# Temp_Bank.net
KiCad netlist of a schematic drawn in Altium Designer
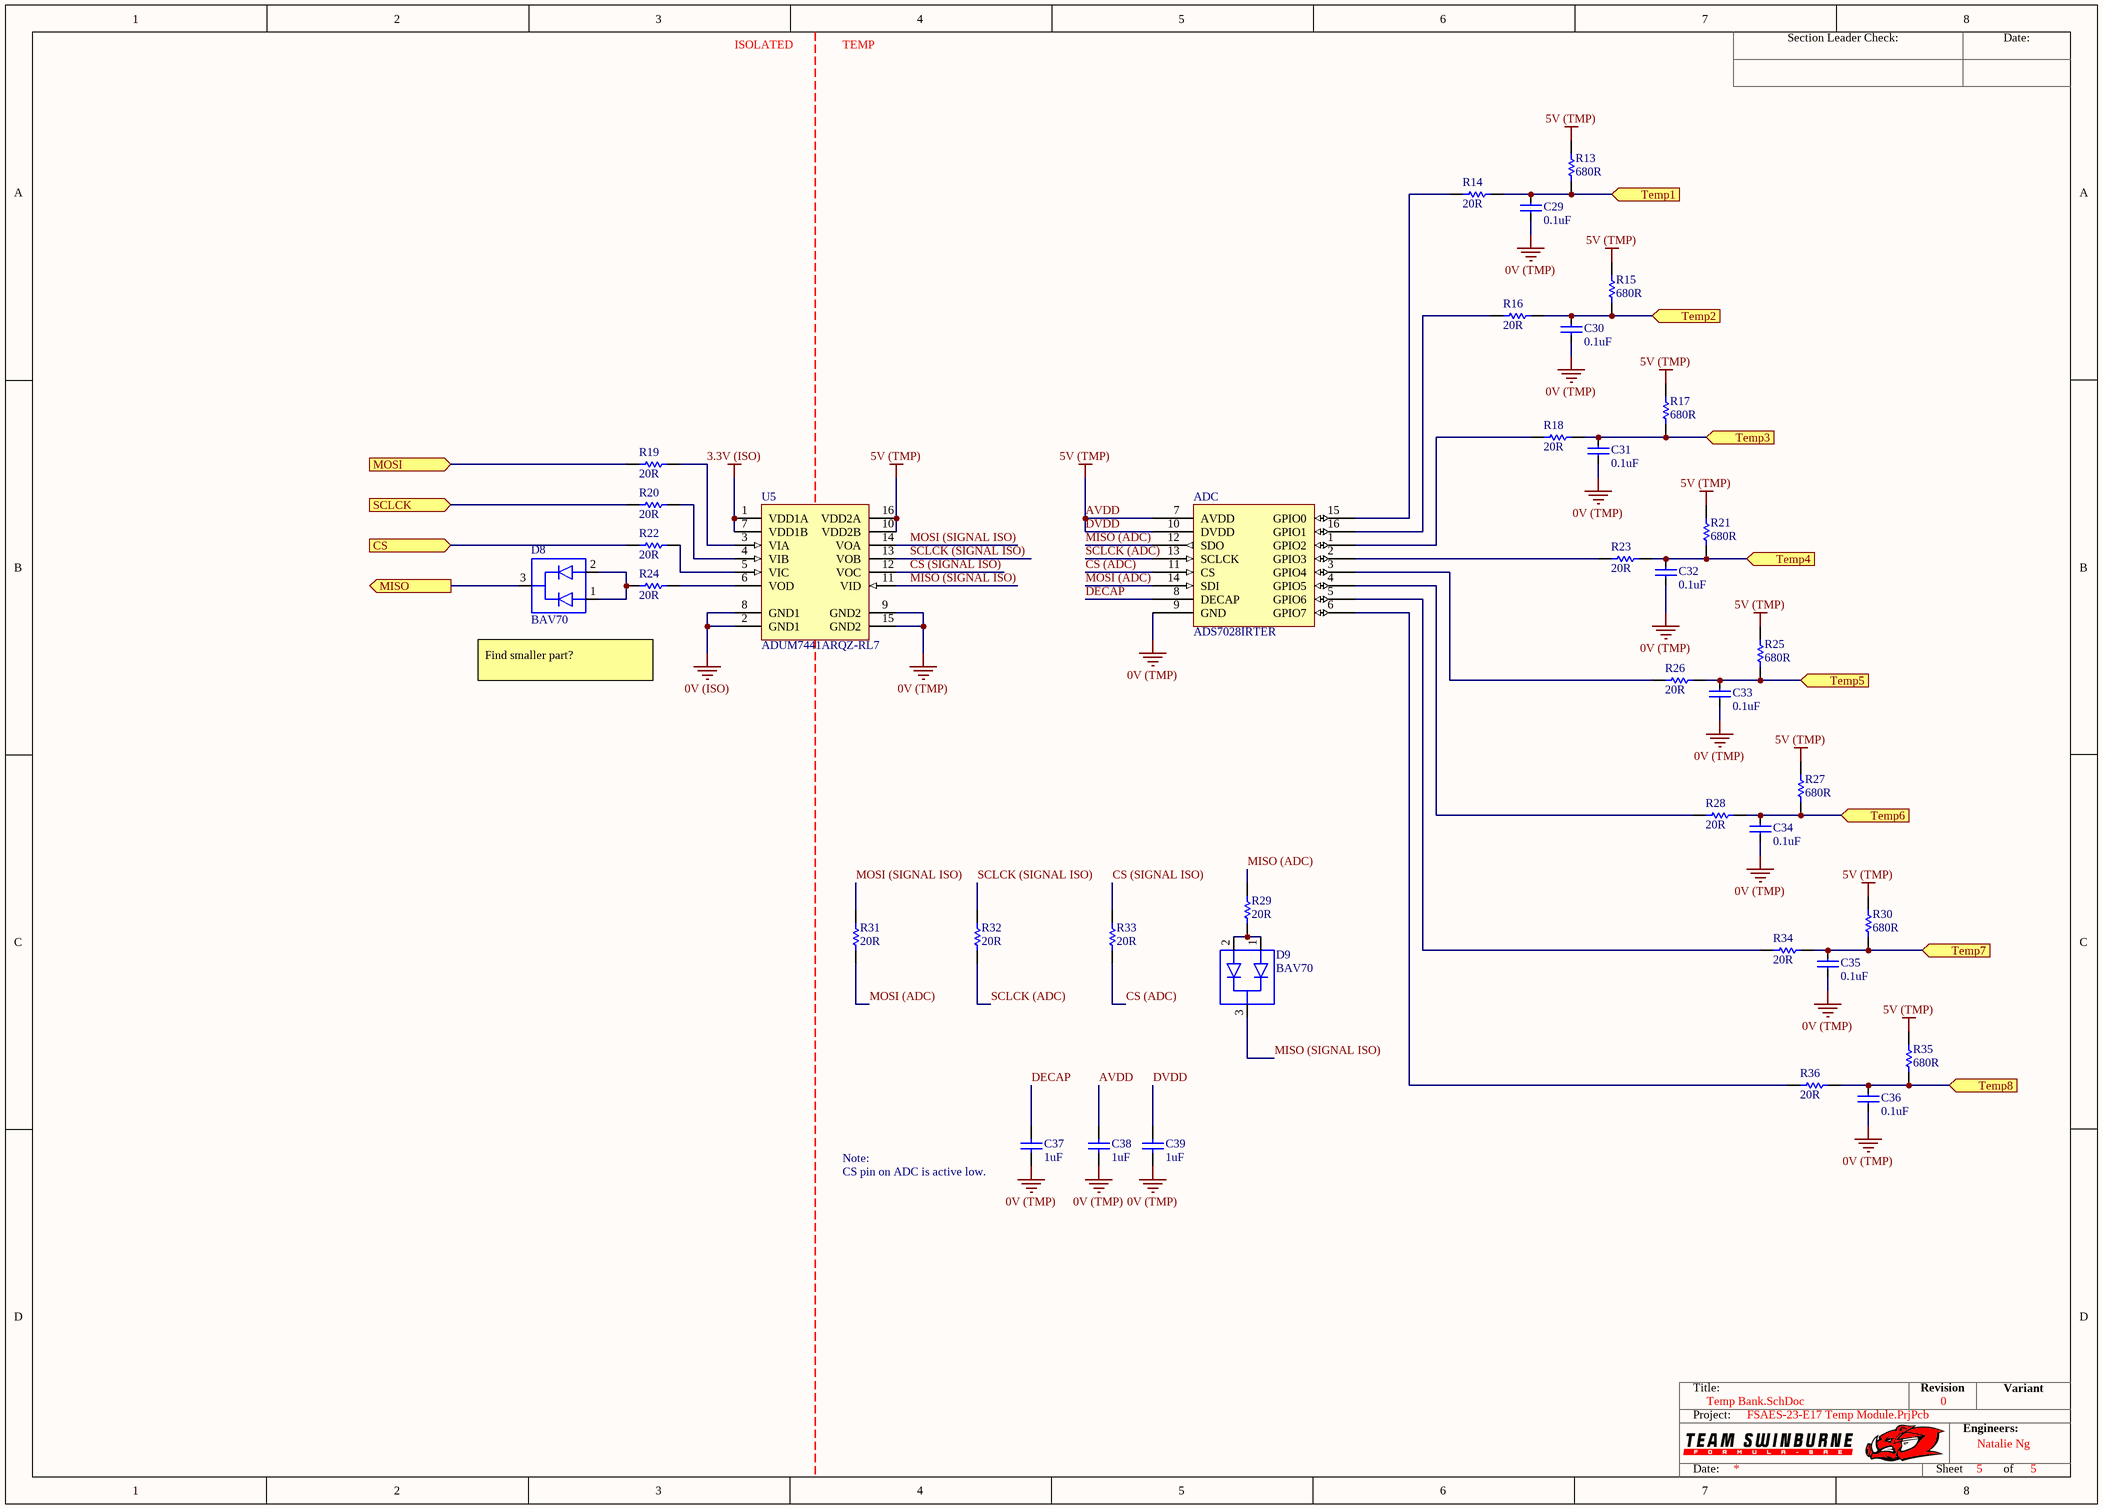
[diagram p0: Temp Bank.SchDoc]

(export (version "E")
  (design (tool "Eeschema 10.0.6"))
  (components
    (comp (ref "ADC")
      (value "ADS7028IRTER")
      (footprint "QFN50P300X300X80_HS-17N")
      (description "Small 8-channel 12-bit analog-to-digital converter (ADC) with SPI, GPIOs and CRC 16-WQFN -40 to 85")
      (libsource (lib "Team Swinburne") (part "ADS7028IRTER-Symbol-1"))
    )
    (comp (ref "C29")
      (value "0.1uF")
      (footprint "0805")
      (description "Cap Ceramic 0.1uF 25V X7R 10% Pad SMD 0805 125C Automotive T/R")
      (fields (field (name "TOLERANCE") "10%"))
      (libsource (lib "Team Swinburne") (part "Capacitors"))
    )
    (comp (ref "C30")
      (value "0.1uF")
      (footprint "0805")
      (description "Cap Ceramic 0.1uF 25V X7R 10% Pad SMD 0805 125C Automotive T/R")
      (fields (field (name "TOLERANCE") "10%"))
      (libsource (lib "Team Swinburne") (part "Capacitors"))
    )
    (comp (ref "C31")
      (value "0.1uF")
      (footprint "0805")
      (description "Cap Ceramic 0.1uF 25V X7R 10% Pad SMD 0805 125C Automotive T/R")
      (fields (field (name "TOLERANCE") "10%"))
      (libsource (lib "Team Swinburne") (part "Capacitors"))
    )
    (comp (ref "C32")
      (value "0.1uF")
      (footprint "0805")
      (description "Cap Ceramic 0.1uF 25V X7R 10% Pad SMD 0805 125C Automotive T/R")
      (fields (field (name "TOLERANCE") "10%"))
      (libsource (lib "Team Swinburne") (part "Capacitors"))
    )
    (comp (ref "C33")
      (value "0.1uF")
      (footprint "0805")
      (description "Cap Ceramic 0.1uF 25V X7R 10% Pad SMD 0805 125C Automotive T/R")
      (fields (field (name "TOLERANCE") "10%"))
      (libsource (lib "Team Swinburne") (part "Capacitors"))
    )
    (comp (ref "C34")
      (value "0.1uF")
      (footprint "0805")
      (description "Cap Ceramic 0.1uF 25V X7R 10% Pad SMD 0805 125C Automotive T/R")
      (fields (field (name "TOLERANCE") "10%"))
      (libsource (lib "Team Swinburne") (part "Capacitors"))
    )
    (comp (ref "C35")
      (value "0.1uF")
      (footprint "0805")
      (description "Cap Ceramic 0.1uF 25V X7R 10% Pad SMD 0805 125C Automotive T/R")
      (fields (field (name "TOLERANCE") "10%"))
      (libsource (lib "Team Swinburne") (part "Capacitors"))
    )
    (comp (ref "C36")
      (value "0.1uF")
      (footprint "0805")
      (description "Cap Ceramic 0.1uF 25V X7R 10% Pad SMD 0805 125C Automotive T/R")
      (fields (field (name "TOLERANCE") "10%"))
      (libsource (lib "Team Swinburne") (part "Capacitors"))
    )
    (comp (ref "C37")
      (value "1uF")
      (footprint "0805")
      (fields
        (field (name "PART NUMBER") "AC0805KKX7R8BB105")
        (field (name "TOLERANCE") "10%")
        (field (name "MANUFACTURER") "YAGEO")
      )
      (libsource (lib "ts_20-standard-library") (part "Capacitor"))
    )
    (comp (ref "C38")
      (value "1uF")
      (footprint "0805")
      (fields
        (field (name "PART NUMBER") "AC0805KKX7R8BB105")
        (field (name "TOLERANCE") "10%")
        (field (name "MANUFACTURER") "YAGEO")
      )
      (libsource (lib "ts_20-standard-library") (part "Capacitor"))
    )
    (comp (ref "C39")
      (value "1uF")
      (footprint "0805")
      (fields
        (field (name "PART NUMBER") "AC0805KKX7R8BB105")
        (field (name "TOLERANCE") "10%")
        (field (name "MANUFACTURER") "YAGEO")
      )
      (libsource (lib "ts_20-standard-library") (part "Capacitor"))
    )
    (comp (ref "D8")
      (value "BAV70")
      (footprint "BAV70-Footprint-1")
      (description "DIODE ARRAY GP 70V 200mA SOT23-3")
      (libsource (lib "Team Swinburne") (part "BAV70-Symbol-1"))
    )
    (comp (ref "D9")
      (value "BAV70")
      (footprint "BAV70-Footprint-1")
      (description "DIODE ARRAY GP 70V 200mA SOT23-3")
      (libsource (lib "Team Swinburne") (part "BAV70-Symbol-1"))
    )
    (comp (ref "R13")
      (value "680R")
      (footprint "0805")
      (description "RC0805FR07680RL")
      (fields (field (name "DIGIKEY PART NUMBER") "311-680CRCT-ND") (field (name "TOLERANCE") "0.01"))
      (libsource (lib "Team Swinburne") (part "Resistor"))
    )
    (comp (ref "R14")
      (value "20R")
      (footprint "RESC0603")
      (description "RES SMD 20 OHM JUMPER 1/10W 0603")
      (fields (field (name "TOLERANCE") "1%"))
      (libsource (lib "Team Swinburne") (part "Resistor"))
    )
    (comp (ref "R15")
      (value "680R")
      (footprint "0805")
      (description "RC0805FR07680RL")
      (fields (field (name "DIGIKEY PART NUMBER") "311-680CRCT-ND") (field (name "TOLERANCE") "0.01"))
      (libsource (lib "Team Swinburne") (part "Resistor"))
    )
    (comp (ref "R16")
      (value "20R")
      (footprint "RESC0603")
      (description "RES SMD 20 OHM JUMPER 1/10W 0603")
      (fields (field (name "TOLERANCE") "1%"))
      (libsource (lib "Team Swinburne") (part "Resistor"))
    )
    (comp (ref "R17")
      (value "680R")
      (footprint "0805")
      (description "RC0805FR07680RL")
      (fields (field (name "DIGIKEY PART NUMBER") "311-680CRCT-ND") (field (name "TOLERANCE") "0.01"))
      (libsource (lib "Team Swinburne") (part "Resistor"))
    )
    (comp (ref "R18")
      (value "20R")
      (footprint "RESC0603")
      (description "RES SMD 20 OHM JUMPER 1/10W 0603")
      (fields (field (name "TOLERANCE") "1%"))
      (libsource (lib "Team Swinburne") (part "Resistor"))
    )
    (comp (ref "R19")
      (value "20R")
      (footprint "RESC0603")
      (description "RES SMD 20 OHM JUMPER 1/10W 0603")
      (fields (field (name "TOLERANCE") "1%"))
      (libsource (lib "Team Swinburne") (part "Resistor"))
    )
    (comp (ref "R20")
      (value "20R")
      (footprint "RESC0603")
      (description "RES SMD 20 OHM JUMPER 1/10W 0603")
      (fields (field (name "TOLERANCE") "1%"))
      (libsource (lib "Team Swinburne") (part "Resistor"))
    )
    (comp (ref "R21")
      (value "680R")
      (footprint "0805")
      (description "RC0805FR07680RL")
      (fields (field (name "DIGIKEY PART NUMBER") "311-680CRCT-ND") (field (name "TOLERANCE") "0.01"))
      (libsource (lib "Team Swinburne") (part "Resistor"))
    )
    (comp (ref "R22")
      (value "20R")
      (footprint "RESC0603")
      (description "RES SMD 20 OHM JUMPER 1/10W 0603")
      (fields (field (name "TOLERANCE") "1%"))
      (libsource (lib "Team Swinburne") (part "Resistor"))
    )
    (comp (ref "R23")
      (value "20R")
      (footprint "RESC0603")
      (description "RES SMD 20 OHM JUMPER 1/10W 0603")
      (fields (field (name "TOLERANCE") "1%"))
      (libsource (lib "Team Swinburne") (part "Resistor"))
    )
    (comp (ref "R24")
      (value "20R")
      (footprint "RESC0603")
      (description "RES SMD 20 OHM JUMPER 1/10W 0603")
      (fields (field (name "TOLERANCE") "1%"))
      (libsource (lib "Team Swinburne") (part "Resistor"))
    )
    (comp (ref "R25")
      (value "680R")
      (footprint "0805")
      (description "RC0805FR07680RL")
      (fields (field (name "DIGIKEY PART NUMBER") "311-680CRCT-ND") (field (name "TOLERANCE") "0.01"))
      (libsource (lib "Team Swinburne") (part "Resistor"))
    )
    (comp (ref "R26")
      (value "20R")
      (footprint "RESC0603")
      (description "RES SMD 20 OHM JUMPER 1/10W 0603")
      (fields (field (name "TOLERANCE") "1%"))
      (libsource (lib "Team Swinburne") (part "Resistor"))
    )
    (comp (ref "R27")
      (value "680R")
      (footprint "0805")
      (description "RC0805FR07680RL")
      (fields (field (name "DIGIKEY PART NUMBER") "311-680CRCT-ND") (field (name "TOLERANCE") "0.01"))
      (libsource (lib "Team Swinburne") (part "Resistor"))
    )
    (comp (ref "R28")
      (value "20R")
      (footprint "RESC0603")
      (description "RES SMD 20 OHM JUMPER 1/10W 0603")
      (fields (field (name "TOLERANCE") "1%"))
      (libsource (lib "Team Swinburne") (part "Resistor"))
    )
    (comp (ref "R29")
      (value "20R")
      (footprint "RESC0603")
      (description "RES SMD 20 OHM JUMPER 1/10W 0603")
      (fields (field (name "TOLERANCE") "1%"))
      (libsource (lib "Team Swinburne") (part "Resistor"))
    )
    (comp (ref "R30")
      (value "680R")
      (footprint "0805")
      (description "RC0805FR07680RL")
      (fields (field (name "DIGIKEY PART NUMBER") "311-680CRCT-ND") (field (name "TOLERANCE") "0.01"))
      (libsource (lib "Team Swinburne") (part "Resistor"))
    )
    (comp (ref "R31")
      (value "20R")
      (footprint "RESC0603")
      (description "RES SMD 20 OHM JUMPER 1/10W 0603")
      (fields (field (name "TOLERANCE") "1%"))
      (libsource (lib "Team Swinburne") (part "Resistor"))
    )
    (comp (ref "R32")
      (value "20R")
      (footprint "RESC0603")
      (description "RES SMD 20 OHM JUMPER 1/10W 0603")
      (fields (field (name "TOLERANCE") "1%"))
      (libsource (lib "Team Swinburne") (part "Resistor"))
    )
    (comp (ref "R33")
      (value "20R")
      (footprint "RESC0603")
      (description "RES SMD 20 OHM JUMPER 1/10W 0603")
      (fields (field (name "TOLERANCE") "1%"))
      (libsource (lib "Team Swinburne") (part "Resistor"))
    )
    (comp (ref "R34")
      (value "20R")
      (footprint "RESC0603")
      (description "RES SMD 20 OHM JUMPER 1/10W 0603")
      (fields (field (name "TOLERANCE") "1%"))
      (libsource (lib "Team Swinburne") (part "Resistor"))
    )
    (comp (ref "R35")
      (value "680R")
      (footprint "0805")
      (description "RC0805FR07680RL")
      (fields (field (name "DIGIKEY PART NUMBER") "311-680CRCT-ND") (field (name "TOLERANCE") "0.01"))
      (libsource (lib "Team Swinburne") (part "Resistor"))
    )
    (comp (ref "R36")
      (value "20R")
      (footprint "RESC0603")
      (description "RES SMD 20 OHM JUMPER 1/10W 0603")
      (fields (field (name "TOLERANCE") "1%"))
      (libsource (lib "Team Swinburne") (part "Resistor"))
    )
    (comp (ref "U5")
      (value "ADUM7441ARQZ-RL7")
      (footprint "ADI-RQ-16_M")
      (description "Digital Isolator CMOS 4-CH 1Mbps 16-Pin QSOP T/R")
      (libsource (lib "Team Swinburne") (part "ADI-ADUM7441-RQ-16"))
    )
  )
  (nets
    (net (code "1") (name "/CS") (class "Default")
      (node (ref "R22") (pin "1") (pinfunction "1_1") (pintype "passive"))
    )
    (net (code "2") (name "/CS (ADC)") (class "Default")
      (node (ref "ADC") (pin "11") (pinfunction "CS_11") (pintype "input"))
      (node (ref "R33") (pin "1") (pinfunction "1_1") (pintype "passive"))
    )
    (net (code "3") (name "/CS (SIGNAL ISO)") (class "Default")
      (node (ref "R33") (pin "2") (pinfunction "2_2") (pintype "passive"))
      (node (ref "U5") (pin "12") (pinfunction "VOC_12") (pintype "tri_state"))
    )
    (net (code "4") (name "/DECAP") (class "Default")
      (node (ref "ADC") (pin "8") (pinfunction "DECAP_8") (pintype "power_in"))
      (node (ref "C37") (pin "2") (pinfunction "2_2") (pintype "passive"))
    )
    (net (code "5") (name "/MISO") (class "Default")
      (node (ref "D8") (pin "3") (pinfunction "CC_3") (pintype "passive"))
    )
    (net (code "6") (name "/MISO (ADC)") (class "Default")
      (node (ref "ADC") (pin "12") (pinfunction "SDO_12") (pintype "output"))
      (node (ref "R29") (pin "2") (pinfunction "2_2") (pintype "passive"))
    )
    (net (code "7") (name "/MISO (SIGNAL ISO)") (class "Default")
      (node (ref "D9") (pin "3") (pinfunction "CC_3") (pintype "passive"))
      (node (ref "U5") (pin "11") (pinfunction "VID_11") (pintype "input"))
    )
    (net (code "8") (name "/MOSI") (class "Default")
      (node (ref "R19") (pin "1") (pinfunction "1_1") (pintype "passive"))
    )
    (net (code "9") (name "/MOSI (ADC)") (class "Default")
      (node (ref "ADC") (pin "14") (pinfunction "SDI_14") (pintype "input"))
      (node (ref "R31") (pin "1") (pinfunction "1_1") (pintype "passive"))
    )
    (net (code "10") (name "/MOSI (SIGNAL ISO)") (class "Default")
      (node (ref "R31") (pin "2") (pinfunction "2_2") (pintype "passive"))
      (node (ref "U5") (pin "14") (pinfunction "VOA_14") (pintype "tri_state"))
    )
    (net (code "11") (name "/SCLCK") (class "Default")
      (node (ref "R20") (pin "1") (pinfunction "1_1") (pintype "passive"))
    )
    (net (code "12") (name "/SCLCK (ADC)") (class "Default")
      (node (ref "ADC") (pin "13") (pinfunction "SCLCK_13") (pintype "input"))
      (node (ref "R32") (pin "1") (pinfunction "1_1") (pintype "passive"))
    )
    (net (code "13") (name "/SCLCK (SIGNAL ISO)") (class "Default")
      (node (ref "R32") (pin "2") (pinfunction "2_2") (pintype "passive"))
      (node (ref "U5") (pin "13") (pinfunction "VOB_13") (pintype "tri_state"))
    )
    (net (code "14") (name "/Temp1") (class "Default")
      (node (ref "C29") (pin "1") (pinfunction "1_1") (pintype "passive"))
      (node (ref "R13") (pin "1") (pinfunction "1_1") (pintype "passive"))
      (node (ref "R14") (pin "2") (pinfunction "2_2") (pintype "passive"))
    )
    (net (code "15") (name "/Temp2") (class "Default")
      (node (ref "C30") (pin "1") (pinfunction "1_1") (pintype "passive"))
      (node (ref "R15") (pin "1") (pinfunction "1_1") (pintype "passive"))
      (node (ref "R16") (pin "2") (pinfunction "2_2") (pintype "passive"))
    )
    (net (code "16") (name "/Temp3") (class "Default")
      (node (ref "C31") (pin "1") (pinfunction "1_1") (pintype "passive"))
      (node (ref "R17") (pin "1") (pinfunction "1_1") (pintype "passive"))
      (node (ref "R18") (pin "2") (pinfunction "2_2") (pintype "passive"))
    )
    (net (code "17") (name "/Temp4") (class "Default")
      (node (ref "C32") (pin "1") (pinfunction "1_1") (pintype "passive"))
      (node (ref "R21") (pin "1") (pinfunction "1_1") (pintype "passive"))
      (node (ref "R23") (pin "2") (pinfunction "2_2") (pintype "passive"))
    )
    (net (code "18") (name "/Temp5") (class "Default")
      (node (ref "C33") (pin "1") (pinfunction "1_1") (pintype "passive"))
      (node (ref "R25") (pin "1") (pinfunction "1_1") (pintype "passive"))
      (node (ref "R26") (pin "2") (pinfunction "2_2") (pintype "passive"))
    )
    (net (code "19") (name "/Temp6") (class "Default")
      (node (ref "C34") (pin "1") (pinfunction "1_1") (pintype "passive"))
      (node (ref "R27") (pin "1") (pinfunction "1_1") (pintype "passive"))
      (node (ref "R28") (pin "2") (pinfunction "2_2") (pintype "passive"))
    )
    (net (code "20") (name "/Temp7") (class "Default")
      (node (ref "C35") (pin "1") (pinfunction "1_1") (pintype "passive"))
      (node (ref "R30") (pin "1") (pinfunction "1_1") (pintype "passive"))
      (node (ref "R34") (pin "2") (pinfunction "2_2") (pintype "passive"))
    )
    (net (code "21") (name "/Temp8") (class "Default")
      (node (ref "C36") (pin "1") (pinfunction "1_1") (pintype "passive"))
      (node (ref "R35") (pin "1") (pinfunction "1_1") (pintype "passive"))
      (node (ref "R36") (pin "2") (pinfunction "2_2") (pintype "passive"))
    )
    (net (code "22") (name "0V (ISO)") (class "Default")
      (node (ref "U5") (pin "2") (pinfunction "GND1_2") (pintype "power_in"))
      (node (ref "U5") (pin "8") (pinfunction "GND1_8") (pintype "power_in"))
    )
    (net (code "23") (name "0V (TMP)") (class "Default")
      (node (ref "ADC") (pin "9") (pinfunction "GND_9") (pintype "power_in"))
      (node (ref "C29") (pin "2") (pinfunction "2_2") (pintype "passive"))
      (node (ref "C30") (pin "2") (pinfunction "2_2") (pintype "passive"))
      (node (ref "C31") (pin "2") (pinfunction "2_2") (pintype "passive"))
      (node (ref "C32") (pin "2") (pinfunction "2_2") (pintype "passive"))
      (node (ref "C33") (pin "2") (pinfunction "2_2") (pintype "passive"))
      (node (ref "C34") (pin "2") (pinfunction "2_2") (pintype "passive"))
      (node (ref "C35") (pin "2") (pinfunction "2_2") (pintype "passive"))
      (node (ref "C36") (pin "2") (pinfunction "2_2") (pintype "passive"))
      (node (ref "C37") (pin "1") (pinfunction "1_1") (pintype "passive"))
      (node (ref "C38") (pin "1") (pinfunction "1_1") (pintype "passive"))
      (node (ref "C39") (pin "1") (pinfunction "1_1") (pintype "passive"))
      (node (ref "U5") (pin "15") (pinfunction "GND2_15") (pintype "power_in"))
      (node (ref "U5") (pin "9") (pinfunction "GND2_9") (pintype "power_in"))
    )
    (net (code "24") (name "3.3V (ISO)") (class "Default")
      (node (ref "U5") (pin "1") (pinfunction "VDD1A_1") (pintype "power_in"))
      (node (ref "U5") (pin "7") (pinfunction "VDD1B_7") (pintype "power_in"))
    )
    (net (code "25") (name "5V (TMP)") (class "Default")
      (node (ref "ADC") (pin "10") (pinfunction "DVDD_10") (pintype "power_in"))
      (node (ref "ADC") (pin "7") (pinfunction "AVDD_7") (pintype "power_in"))
      (node (ref "C38") (pin "2") (pinfunction "2_2") (pintype "passive"))
      (node (ref "C39") (pin "2") (pinfunction "2_2") (pintype "passive"))
      (node (ref "R13") (pin "2") (pinfunction "2_2") (pintype "passive"))
      (node (ref "R15") (pin "2") (pinfunction "2_2") (pintype "passive"))
      (node (ref "R17") (pin "2") (pinfunction "2_2") (pintype "passive"))
      (node (ref "R21") (pin "2") (pinfunction "2_2") (pintype "passive"))
      (node (ref "R25") (pin "2") (pinfunction "2_2") (pintype "passive"))
      (node (ref "R27") (pin "2") (pinfunction "2_2") (pintype "passive"))
      (node (ref "R30") (pin "2") (pinfunction "2_2") (pintype "passive"))
      (node (ref "R35") (pin "2") (pinfunction "2_2") (pintype "passive"))
      (node (ref "U5") (pin "10") (pinfunction "VDD2B_10") (pintype "power_in"))
      (node (ref "U5") (pin "16") (pinfunction "VDD2A_16") (pintype "power_in"))
    )
    (net (code "26") (name "Net-(ADC-GPIO0)") (class "Default")
      (node (ref "ADC") (pin "15") (pinfunction "GPIO0_15") (pintype "bidirectional"))
      (node (ref "R14") (pin "1") (pinfunction "1_1") (pintype "passive"))
    )
    (net (code "27") (name "Net-(ADC-GPIO1)") (class "Default")
      (node (ref "ADC") (pin "16") (pinfunction "GPIO1_16") (pintype "bidirectional"))
      (node (ref "R16") (pin "1") (pinfunction "1_1") (pintype "passive"))
    )
    (net (code "28") (name "Net-(ADC-GPIO2)") (class "Default")
      (node (ref "ADC") (pin "1") (pinfunction "GPIO2_1") (pintype "bidirectional"))
      (node (ref "R18") (pin "1") (pinfunction "1_1") (pintype "passive"))
    )
    (net (code "29") (name "Net-(ADC-GPIO3)") (class "Default")
      (node (ref "ADC") (pin "2") (pinfunction "GPIO3_2") (pintype "bidirectional"))
      (node (ref "R23") (pin "1") (pinfunction "1_1") (pintype "passive"))
    )
    (net (code "30") (name "Net-(ADC-GPIO4)") (class "Default")
      (node (ref "ADC") (pin "3") (pinfunction "GPIO4_3") (pintype "bidirectional"))
      (node (ref "R26") (pin "1") (pinfunction "1_1") (pintype "passive"))
    )
    (net (code "31") (name "Net-(ADC-GPIO5)") (class "Default")
      (node (ref "ADC") (pin "4") (pinfunction "GPIO5_4") (pintype "bidirectional"))
      (node (ref "R28") (pin "1") (pinfunction "1_1") (pintype "passive"))
    )
    (net (code "32") (name "Net-(ADC-GPIO6)") (class "Default")
      (node (ref "ADC") (pin "5") (pinfunction "GPIO6_5") (pintype "bidirectional"))
      (node (ref "R34") (pin "1") (pinfunction "1_1") (pintype "passive"))
    )
    (net (code "33") (name "Net-(ADC-GPIO7)") (class "Default")
      (node (ref "ADC") (pin "6") (pinfunction "GPIO7_6") (pintype "bidirectional"))
      (node (ref "R36") (pin "1") (pinfunction "1_1") (pintype "passive"))
    )
    (net (code "34") (name "Net-(D8-A1)") (class "Default")
      (node (ref "D8") (pin "1") (pinfunction "A1_1") (pintype "passive"))
      (node (ref "D8") (pin "2") (pinfunction "A2_2") (pintype "passive"))
      (node (ref "R24") (pin "1") (pinfunction "1_1") (pintype "passive"))
    )
    (net (code "35") (name "Net-(D9-A1)") (class "Default")
      (node (ref "D9") (pin "1") (pinfunction "A1_1") (pintype "passive"))
      (node (ref "D9") (pin "2") (pinfunction "A2_2") (pintype "passive"))
      (node (ref "R29") (pin "1") (pinfunction "1_1") (pintype "passive"))
    )
    (net (code "36") (name "Net-(U5-VIA)") (class "Default")
      (node (ref "R19") (pin "2") (pinfunction "2_2") (pintype "passive"))
      (node (ref "U5") (pin "3") (pinfunction "VIA_3") (pintype "input"))
    )
    (net (code "37") (name "Net-(U5-VIB)") (class "Default")
      (node (ref "R20") (pin "2") (pinfunction "2_2") (pintype "passive"))
      (node (ref "U5") (pin "4") (pinfunction "VIB_4") (pintype "input"))
    )
    (net (code "38") (name "Net-(U5-VIC)") (class "Default")
      (node (ref "R22") (pin "2") (pinfunction "2_2") (pintype "passive"))
      (node (ref "U5") (pin "5") (pinfunction "VIC_5") (pintype "input"))
    )
    (net (code "39") (name "Net-(U5-VOD)") (class "Default")
      (node (ref "R24") (pin "2") (pinfunction "2_2") (pintype "passive"))
      (node (ref "U5") (pin "6") (pinfunction "VOD_6") (pintype "tri_state"))
    )
  )
)
